# LM7805.net
KiCad netlist of a schematic drawn in EAGLE
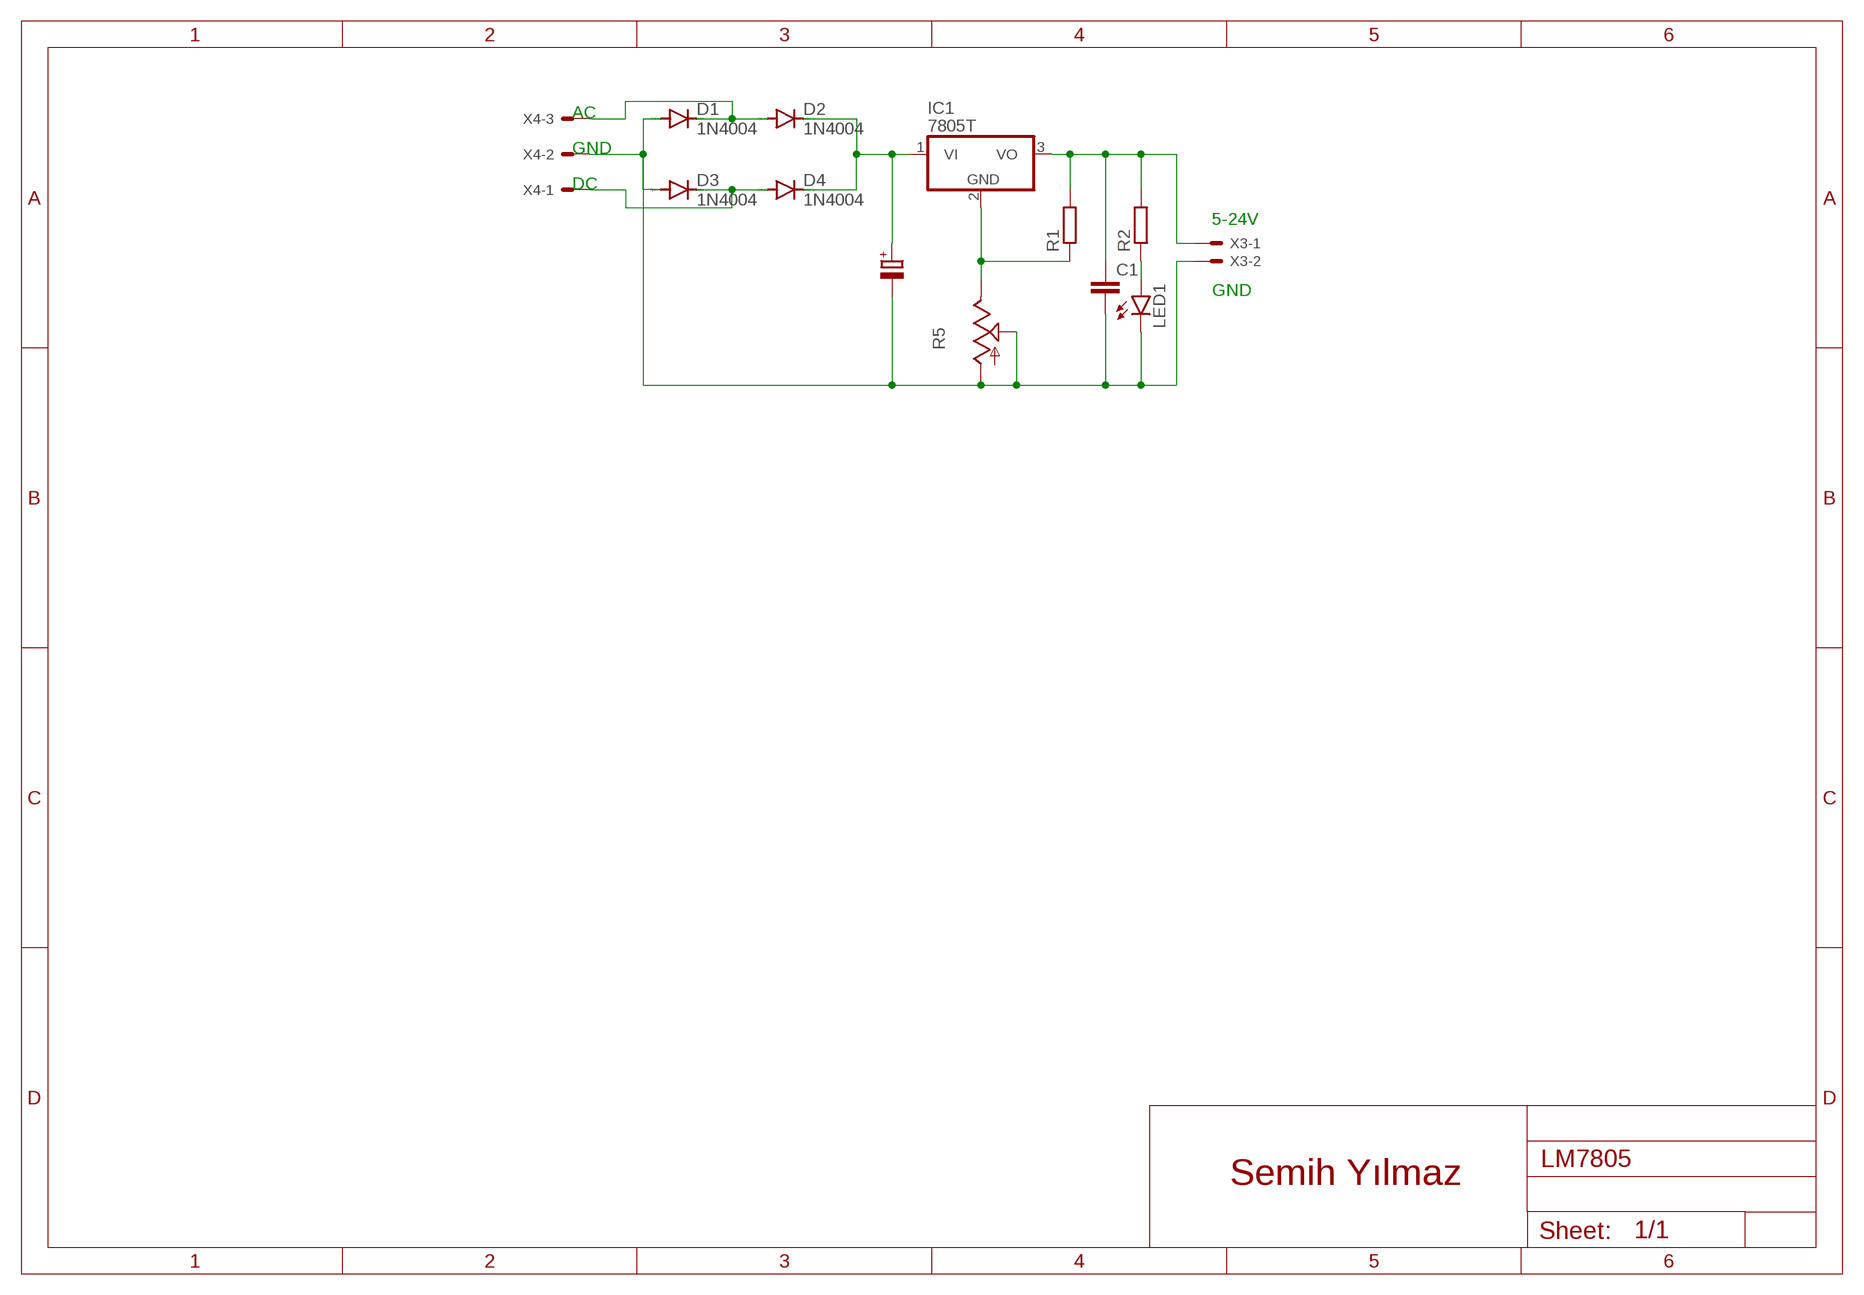
[diagram p0: schematic, sheet 1]

(export (version "E")
  (design (tool "Eeschema 10.0.6"))
  (components
    (comp (ref "C1")
      (value "C2.5/2")
      (footprint "eagle-import:C2.5-2")
      (libsource (lib "eagle-import") (part "C2.5/2"))
    )
    (comp (ref "D1")
      (value "1N4004")
      (footprint "eagle-import:DO41-10")
      (libsource (lib "eagle-import") (part "1N4004"))
    )
    (comp (ref "D2")
      (value "1N4004")
      (footprint "eagle-import:DO41-10")
      (libsource (lib "eagle-import") (part "1N4004"))
    )
    (comp (ref "D3")
      (value "1N4004")
      (footprint "eagle-import:DO41-10")
      (libsource (lib "eagle-import") (part "1N4004"))
    )
    (comp (ref "D4")
      (value "1N4004")
      (footprint "eagle-import:DO41-10")
      (libsource (lib "eagle-import") (part "1N4004"))
    )
    (comp (ref "IC1")
      (value "7805T")
      (footprint "eagle-import:TO220H")
      (libsource (lib "eagle-import") (part "78T05"))
    )
    (comp (ref "LED1")
      (value "LED3MM")
      (footprint "eagle-import:LED3MM")
      (libsource (lib "eagle-import") (part "LED3MM"))
    )
    (comp (ref "R1")
      (value "R-EU_0204/7")
      (footprint "eagle-import:0204_7")
      (libsource (lib "eagle-import") (part "R-EU_0204/7"))
    )
    (comp (ref "R2")
      (value "R-EU_0204/7")
      (footprint "eagle-import:0204_7")
      (libsource (lib "eagle-import") (part "R-EU_0204/7"))
    )
    (comp (ref "R5")
      (value "TRIM_US-S64W")
      (footprint "eagle-import:S64W")
      (libsource (lib "eagle-import") (part "TRIM_US-S64W"))
    )
    (comp (ref "X3")
      (value "22-23-2021")
      (footprint "eagle-import:22-23-2021")
      (fields (field (name "MF") "MOLEX"))
      (libsource (lib "eagle-import") (part "22-23-2021"))
    )
    (comp (ref "X4")
      (value "22-23-2031")
      (footprint "eagle-import:22-23-2031")
      (fields (field (name "MF") "MOLEX"))
      (libsource (lib "eagle-import") (part "22-23-2031"))
    )
  )
  (nets
    (net (code "1") (name "Net-(IC1-GND)") (class "Default")
      (node (ref "IC1") (pin "2") (pinfunction "GND_2") (pintype "passive"))
      (node (ref "R1") (pin "1") (pinfunction "1_1") (pintype "passive"))
      (node (ref "R5") (pin "E") (pinfunction "E_E") (pintype "passive"))
    )
    (net (code "2") (name "Net-(IC1-VI)") (class "Default")
      (node (ref "D2") (pin "C") (pinfunction "C_C") (pintype "passive"))
      (node (ref "D4") (pin "C") (pinfunction "C_C") (pintype "passive"))
      (node (ref "IC1") (pin "1") (pinfunction "VI_1") (pintype "input"))
    )
    (net (code "3") (name "Net-(IC1-VO)") (class "Default")
      (node (ref "C1") (pin "1") (pinfunction "1_1") (pintype "passive"))
      (node (ref "IC1") (pin "3") (pinfunction "VO_3") (pintype "passive"))
      (node (ref "R1") (pin "2") (pinfunction "2_2") (pintype "passive"))
      (node (ref "R2") (pin "2") (pinfunction "2_2") (pintype "passive"))
      (node (ref "X3") (pin "1") (pinfunction "S_1") (pintype "passive"))
    )
    (net (code "4") (name "Net-(LED1-C)") (class "Default")
      (node (ref "C1") (pin "2") (pinfunction "2_2") (pintype "passive"))
      (node (ref "D1") (pin "A") (pinfunction "A_A") (pintype "passive"))
      (node (ref "D3") (pin "A") (pinfunction "A_A") (pintype "passive"))
      (node (ref "LED1") (pin "K") (pinfunction "C_K") (pintype "passive"))
      (node (ref "R5") (pin "A") (pinfunction "A_A") (pintype "passive"))
      (node (ref "R5") (pin "S") (pinfunction "S_S") (pintype "passive"))
      (node (ref "X3") (pin "2") (pinfunction "S_2") (pintype "passive"))
      (node (ref "X4") (pin "2") (pinfunction "S_2") (pintype "passive"))
    )
    (net (code "5") (name "Net-(LED1-PadA)") (class "Default")
      (node (ref "LED1") (pin "A") (pinfunction "A_A") (pintype "passive"))
      (node (ref "R2") (pin "1") (pinfunction "1_1") (pintype "passive"))
    )
    (net (code "6") (name "Net-(X4A-S)") (class "Default")
      (node (ref "D3") (pin "C") (pinfunction "C_C") (pintype "passive"))
      (node (ref "D4") (pin "A") (pinfunction "A_A") (pintype "passive"))
      (node (ref "X4") (pin "1") (pinfunction "S_1") (pintype "passive"))
    )
    (net (code "7") (name "Net-(X4C-S)") (class "Default")
      (node (ref "D1") (pin "C") (pinfunction "C_C") (pintype "passive"))
      (node (ref "D2") (pin "A") (pinfunction "A_A") (pintype "passive"))
      (node (ref "X4") (pin "3") (pinfunction "S_3") (pintype "passive"))
    )
  )
)
